# pca10028_power_supply.net
KiCad netlist of a schematic drawn in Altium Designer
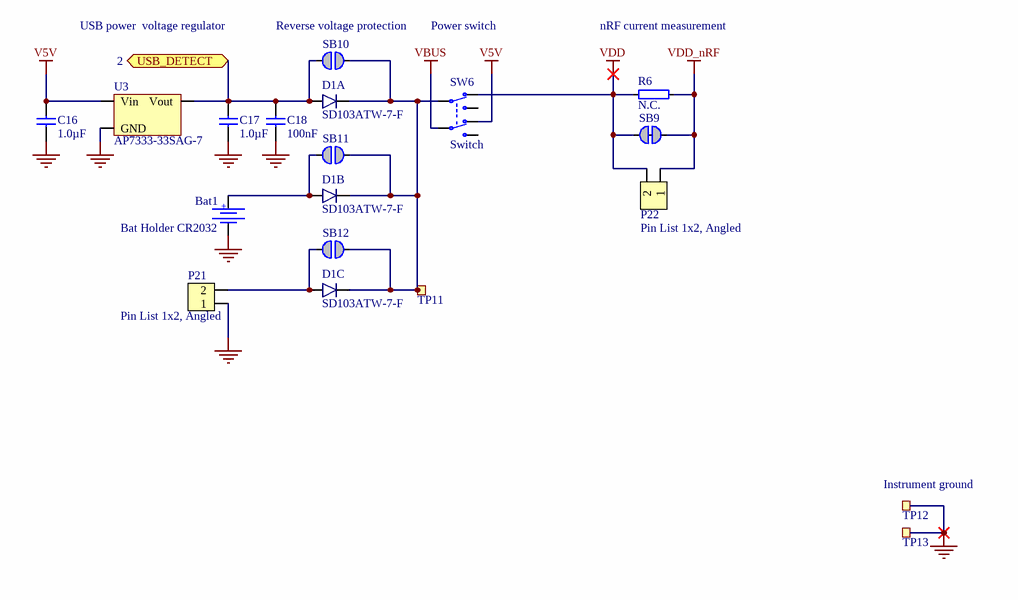
[diagram p0: pca10028_power_supply.SchDoc]

(export (version "E")
  (design (tool "Eeschema 10.0.6"))
  (components
    (comp (ref "Bat1")
      (value "Bat Holder CR2032")
      (footprint "CR2032_HOLDER_SMD")
      (description "Bat Holder CR2032 SMD")
      (fields
        (field (name "MANUFACTURER") "Keystone")
        (field (name "MANUFACTURER PART NUMBER") "3002")
        (field (name "PUBLISHER") "Nordic Semiconductor")
      )
      (libsource (lib "Nordic Passive DB") (part "Battery"))
    )
    (comp (ref "C16")
      (value "1.0µF")
      (footprint "CAPC1608X06L")
      (description "Capacitor, X7R, ±10%")
      (fields (field (name "PART NUMBER") "C0603-1µ0") (field (name "PUBLISHER") "Nordic Semiconductor"))
      (libsource (lib "Nordic Passive DB") (part "CAP"))
    )
    (comp (ref "C17")
      (value "1.0µF")
      (footprint "CAPC1608X06L")
      (description "Capacitor, X7R, ±10%")
      (fields (field (name "PART NUMBER") "C0603-1µ0") (field (name "PUBLISHER") "Nordic Semiconductor"))
      (libsource (lib "Nordic Passive DB") (part "CAP"))
    )
    (comp (ref "C18")
      (value "100nF")
      (footprint "CAPC1005X04L")
      (description "Capacitor, X7R, ±10%")
      (fields (field (name "PART NUMBER") "C0402-100n") (field (name "PUBLISHER") "Nordic Semiconductor"))
      (libsource (lib "Nordic Passive DB") (part "CAP"))
    )
    (comp (ref "D1")
      (value "SD103ATW-7-F")
      (footprint "SOT-363")
      (description "Surface Mount Schottky Barrier Diode Array")
      (fields
        (field (name "MANUFACTURER") "Diodes Incorporated")
        (field (name "2ND SOURCE PART NUMBER") "177-3507")
        (field (name "PUBLISHER") "Nordic Semiconductor")
      )
      (libsource (lib "Nordic Discrete DB") (part "D{colon}DIODE_3_IND"))
    )
    (comp (ref "P21")
      (value "Pin List 1x2, Angled")
      (footprint "LIST_ANG_1x2-SMD-2.54MM")
      (description "Pin List 1x2, 2.54mm (100mil), Right Angled, SMD")
      (fields
        (field (name "PART NUMBER") "Pin List Ang 1x2 SMD, 2.54mm")
        (field (name "2ND SOURCE PART NUMBER") "S1113E-02-ND")
        (field (name "PUBLISHER") "Nordic Semiconductor")
      )
      (libsource (lib "") (part "CONN-2_1"))
    )
    (comp (ref "P22")
      (value "Pin List 1x2, Angled")
      (footprint "LIST_ANG_1x2-SMD-2.54MM")
      (description "Pin List 1x2, 2.54mm (100mil), Right Angled, SMD")
      (fields
        (field (name "PART NUMBER") "Pin List Ang 1x2 SMD, 2.54mm")
        (field (name "2ND SOURCE PART NUMBER") "S1113E-02-ND")
        (field (name "PUBLISHER") "Nordic Semiconductor")
      )
      (libsource (lib "Nordic Passive DB") (part "CONN-2"))
    )
    (comp (ref "R6")
      (value "N.C.")
      (footprint "RESC1005X04L")
      (description "Not mounted")
      (fields (field (name "PART NUMBER") "R0402-N.C.") (field (name "PUBLISHER") "Nordic Semiconductor"))
      (libsource (lib "Nordic Passive DB") (part "RES_1"))
    )
    (comp (ref "SB9")
      (value "Solderbridge")
      (footprint "Solderbridge_Shorted")
      (description "Shorted Solderbridge")
      (fields
        (field (name "PART NUMBER") "Solderbridge Shorted")
        (field (name "PUBLISHER") "Nordic Semiconductor")
      )
      (libsource (lib "Nordic Passive DB") (part "SOLDERBRIDGE_SHORTED"))
    )
    (comp (ref "SB10")
      (value "Solderbridge")
      (footprint "Solderbridge")
      (fields (field (name "PUBLISHER") "Nordic Semiconductor"))
      (libsource (lib "Nordic Passive DB") (part "SOLDERBRIDGE"))
    )
    (comp (ref "SB11")
      (value "Solderbridge")
      (footprint "Solderbridge")
      (fields (field (name "PUBLISHER") "Nordic Semiconductor"))
      (libsource (lib "Nordic Passive DB") (part "SOLDERBRIDGE"))
    )
    (comp (ref "SB12")
      (value "Solderbridge")
      (footprint "Solderbridge")
      (fields (field (name "PUBLISHER") "Nordic Semiconductor"))
      (libsource (lib "Nordic Passive DB") (part "SOLDERBRIDGE"))
    )
    (comp (ref "SW6")
      (value "Switch")
      (footprint "JS202011SCQN")
      (description "SMD slide Switch (ON-ON)")
      (fields
        (field (name "PART NUMBER") "JS202011SCQN")
        (field (name "MANUFACTURER") "C&K Components")
        (field (name "PUBLISHER") "Nordic Semiconductor")
      )
      (libsource (lib "Nordic Discrete DB") (part "SW-DPDT"))
    )
    (comp (ref "TP11")
      (value "Ø1.0mm,SMD")
      (footprint "TP_SMD_Ø1.0mm")
      (description "1.0mm circular SMD testpad")
      (fields
        (field (name "PART NUMBER") "TP_SMD_Ø1.0MM")
        (field (name "MANUFACTURER") "Nordic Semiconductor")
        (field (name "PUBLISHER") "Nordic Semiconductor")
      )
      (libsource (lib "Nordic Passive DB") (part "TESTPAD"))
    )
    (comp (ref "TP12")
      (value "TP")
      (footprint "TESTPAD-TH")
      (description "Testpoint, through hole")
      (fields (field (name "PART NUMBER") "Testpoint TH") (field (name "PUBLISHER") "Nordic Semiconductor"))
      (libsource (lib "") (part "TESTPAD_1"))
    )
    (comp (ref "TP13")
      (value "TP")
      (footprint "TESTPAD-TH")
      (description "Testpoint, through hole")
      (fields (field (name "PART NUMBER") "Testpoint TH") (field (name "PUBLISHER") "Nordic Semiconductor"))
      (libsource (lib "") (part "TESTPAD_1"))
    )
    (comp (ref "U3")
      (value "AP7333-33SAG-7")
      (footprint "SOT-23A")
      (description "300mA, Low Quiescent Current, Fast Transient Low Dropout Linear Regulator")
      (fields
        (field (name "MANUFACTURER") "Diodes Incorporated")
        (field (name "PUBLISHER") "Nordic Semiconductor")
      )
      (libsource (lib "Nordic Active DB") (part "AP7333-XXSAG"))
    )
  )
  (nets
    (net (code "1") (name "/USB_DETECT") (class "Default")
      (node (ref "C17") (pin "2") (pinfunction "2_2") (pintype "passive"))
      (node (ref "C18") (pin "2") (pinfunction "2_2") (pintype "passive"))
      (node (ref "D1") (pin "6") (pinfunction "A1_6") (pintype "passive"))
      (node (ref "SB10") (pin "2") (pinfunction "1_2") (pintype "passive"))
      (node (ref "U3") (pin "2") (pinfunction "Vout_2") (pintype "passive"))
    )
    (net (code "2") (name "GND") (class "Default")
      (node (ref "Bat1") (pin "2") (pintype "passive"))
      (node (ref "C16") (pin "1") (pinfunction "1_1") (pintype "passive"))
      (node (ref "C17") (pin "1") (pinfunction "1_1") (pintype "passive"))
      (node (ref "C18") (pin "1") (pinfunction "1_1") (pintype "passive"))
      (node (ref "P21") (pin "1") (pinfunction "1_1") (pintype "passive"))
      (node (ref "TP12") (pin "1") (pinfunction "1_1") (pintype "passive"))
      (node (ref "TP13") (pin "1") (pinfunction "1_1") (pintype "passive"))
      (node (ref "U3") (pin "3") (pinfunction "GND_3") (pintype "passive"))
    )
    (net (code "3") (name "Net-(D1A-C1)") (class "Default")
      (node (ref "D1") (pin "1") (pinfunction "C1_1") (pintype "passive"))
      (node (ref "D1") (pin "2") (pinfunction "C2_2") (pintype "passive"))
      (node (ref "D1") (pin "3") (pinfunction "C3_3") (pintype "passive"))
      (node (ref "SB10") (pin "1") (pinfunction "0_1") (pintype "passive"))
      (node (ref "SB11") (pin "1") (pinfunction "0_1") (pintype "passive"))
      (node (ref "SB12") (pin "1") (pinfunction "0_1") (pintype "passive"))
      (node (ref "SW6") (pin "2") (pinfunction "COM-1_2") (pintype "passive"))
      (node (ref "TP11") (pin "1") (pinfunction "1_1") (pintype "passive"))
    )
    (net (code "4") (name "Net-(D1B-A2)") (class "Default")
      (node (ref "Bat1") (pin "1") (pintype "passive"))
      (node (ref "D1") (pin "5") (pinfunction "A2_5") (pintype "passive"))
      (node (ref "SB11") (pin "2") (pinfunction "1_2") (pintype "passive"))
    )
    (net (code "5") (name "Net-(D1C-A3)") (class "Default")
      (node (ref "D1") (pin "4") (pinfunction "A3_4") (pintype "passive"))
      (node (ref "P21") (pin "2") (pinfunction "2_2") (pintype "passive"))
      (node (ref "SB12") (pin "2") (pinfunction "1_2") (pintype "passive"))
    )
    (net (code "6") (name "V5V") (class "Default")
      (node (ref "C16") (pin "2") (pinfunction "2_2") (pintype "passive"))
      (node (ref "SW6") (pin "6") (pinfunction "N.C-2_6") (pintype "passive"))
      (node (ref "U3") (pin "1") (pinfunction "Vin_1") (pintype "passive"))
    )
    (net (code "7") (name "VBUS") (class "Default")
      (node (ref "SW6") (pin "5") (pinfunction "COM-2_5") (pintype "passive"))
    )
    (net (code "8") (name "VDD") (class "Default")
      (node (ref "P22") (pin "2") (pinfunction "2_2") (pintype "passive"))
      (node (ref "R6") (pin "1") (pinfunction "1_1") (pintype "passive"))
      (node (ref "SB9") (pin "2") (pinfunction "1_2") (pintype "passive"))
      (node (ref "SW6") (pin "3") (pinfunction "N.C-1_3") (pintype "passive"))
    )
    (net (code "9") (name "VDD_nRF") (class "Default")
      (node (ref "P22") (pin "1") (pinfunction "1_1") (pintype "passive"))
      (node (ref "R6") (pin "2") (pinfunction "2_2") (pintype "passive"))
      (node (ref "SB9") (pin "1") (pinfunction "0_1") (pintype "passive"))
    )
    (net (code "10") (name "unconnected-(SW6-N.O-1-Pad1)") (class "Default")
      (node (ref "SW6") (pin "1") (pinfunction "N.O-1_1") (pintype "passive"))
    )
    (net (code "11") (name "unconnected-(SW6-N.O-2-Pad4)") (class "Default")
      (node (ref "SW6") (pin "4") (pinfunction "N.O-2_4") (pintype "passive"))
    )
  )
)
